# 737NG_CDU_MainPanel_v_01.net
KiCad netlist of a schematic drawn in EasyEDA
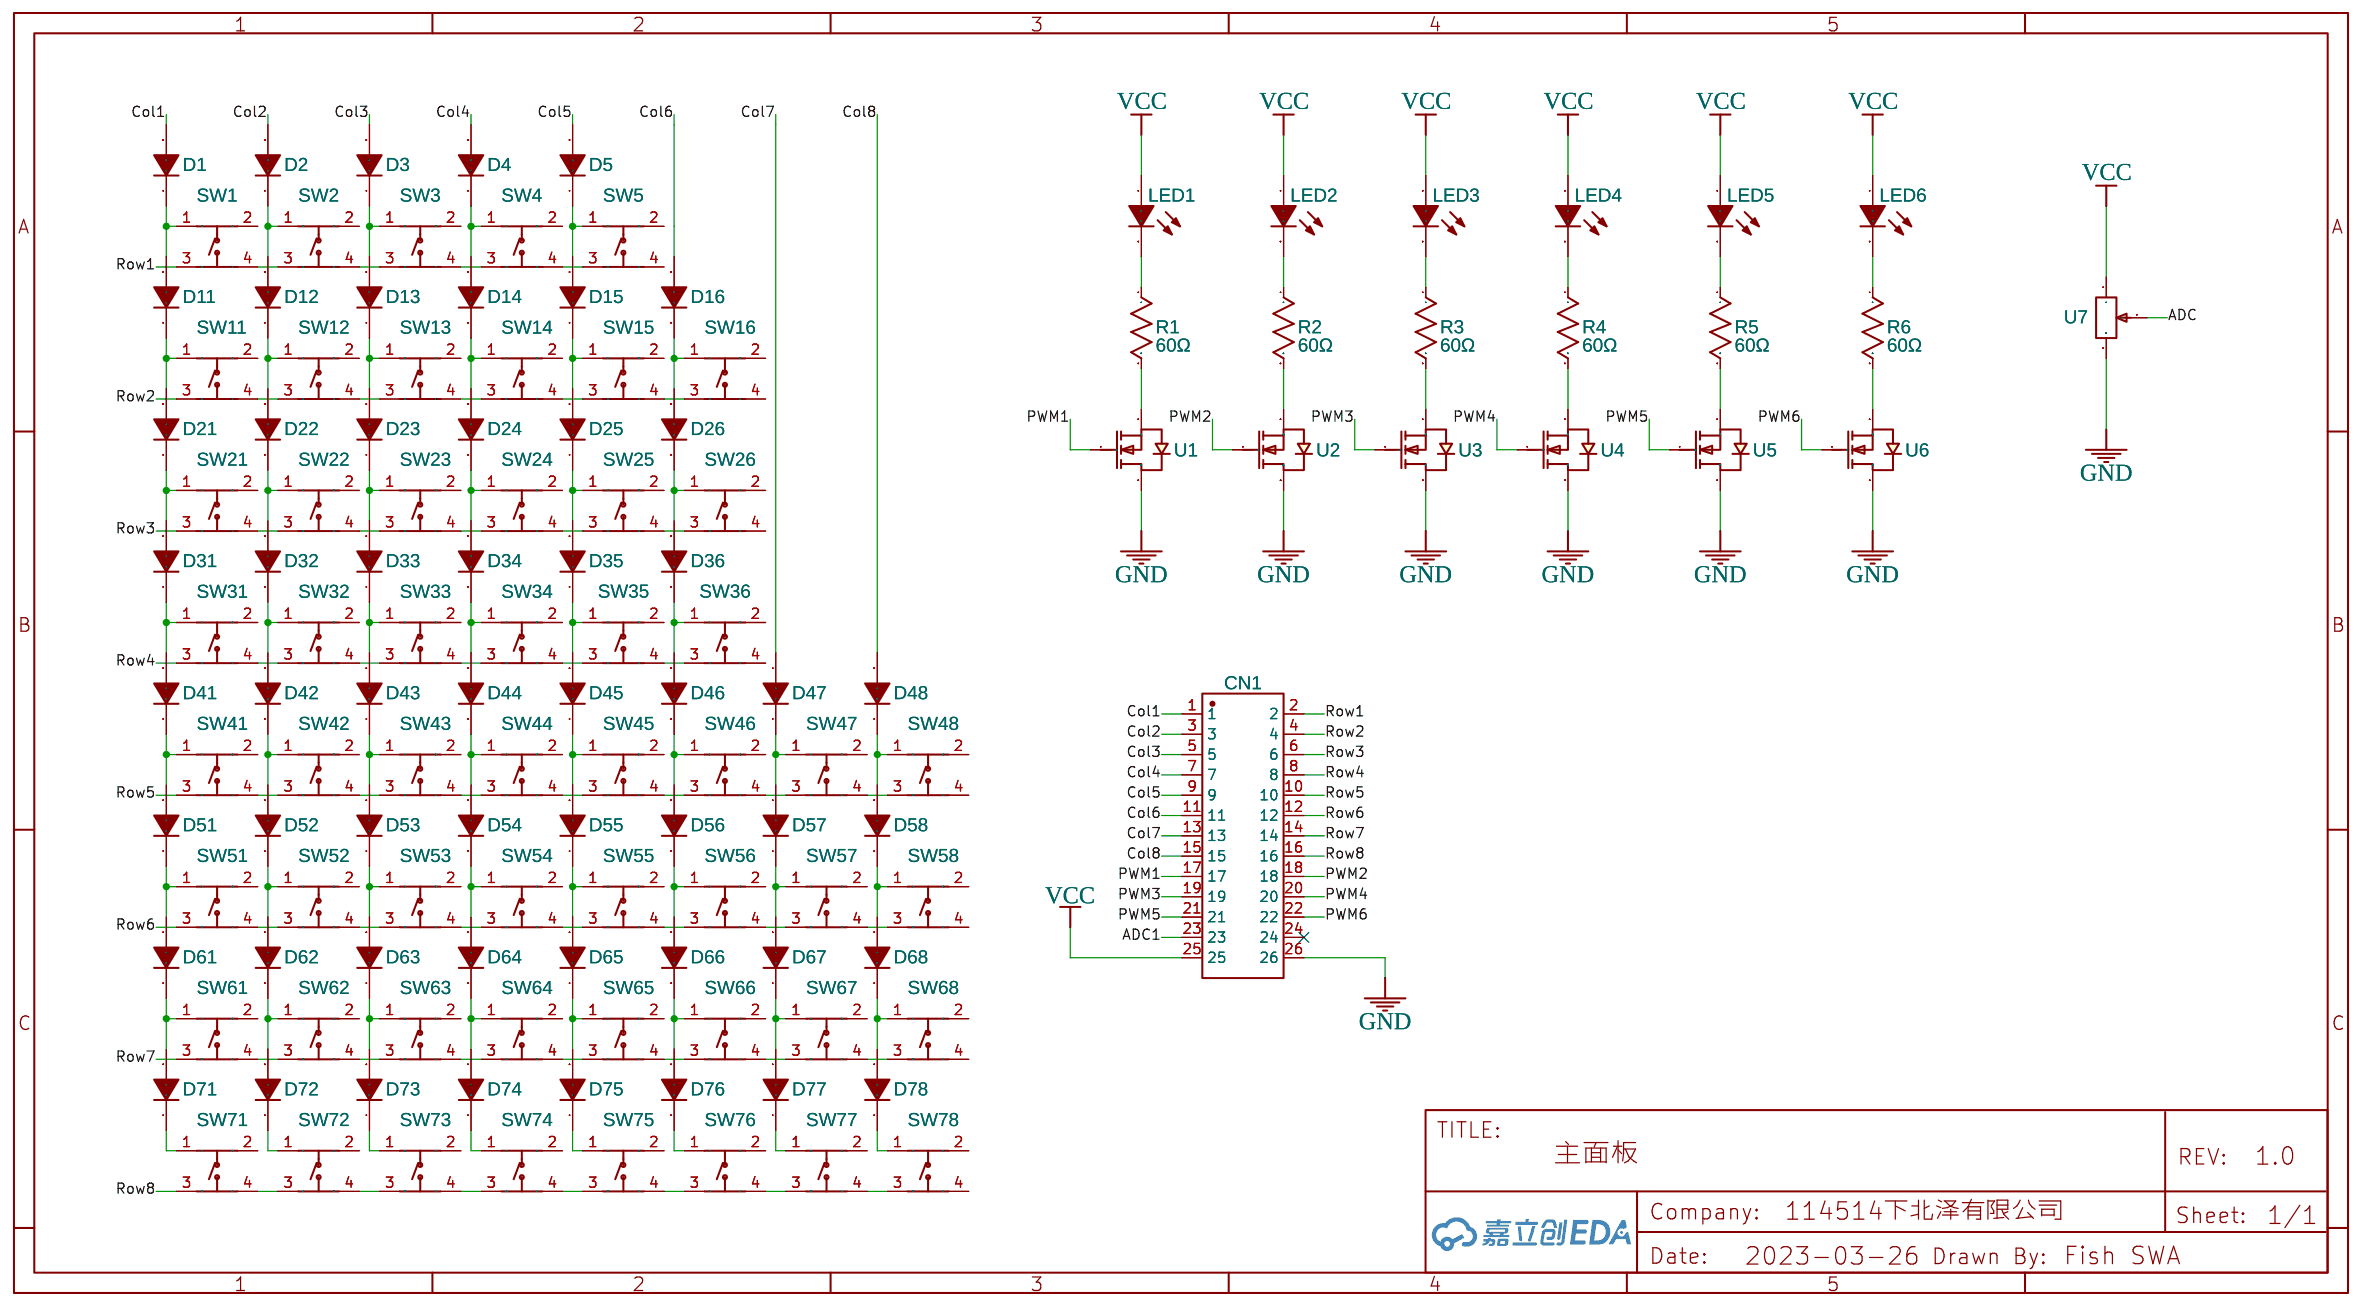
[diagram p0: schematic sheet]

(export (version "E")
  (design (tool "Eeschema 10.0.6"))
  (components
    (comp (ref "CN1")
      (value "A2004WV-2X13P")
      (fields (field (name "BOM_Supplier Part") "C465323"))
      (libsource (lib "") (part "A2004WV-2X13P"))
    )
    (comp (ref "D1")
      (value "1N4148WS T4")
      (fields (field (name "BOM_Manufacturer Part") "1N4148WS") (field (name "BOM_Supplier Part") "C2128"))
      (libsource (lib "") (part "1N4148WS T4"))
    )
    (comp (ref "D2")
      (value "1N4148WS T4")
      (fields (field (name "BOM_Manufacturer Part") "1N4148WS") (field (name "BOM_Supplier Part") "C2128"))
      (libsource (lib "") (part "1N4148WS T4"))
    )
    (comp (ref "D3")
      (value "1N4148WS T4")
      (fields (field (name "BOM_Manufacturer Part") "1N4148WS") (field (name "BOM_Supplier Part") "C2128"))
      (libsource (lib "") (part "1N4148WS T4"))
    )
    (comp (ref "D4")
      (value "1N4148WS T4")
      (fields (field (name "BOM_Manufacturer Part") "1N4148WS") (field (name "BOM_Supplier Part") "C2128"))
      (libsource (lib "") (part "1N4148WS T4"))
    )
    (comp (ref "D5")
      (value "1N4148WS T4")
      (fields (field (name "BOM_Manufacturer Part") "1N4148WS") (field (name "BOM_Supplier Part") "C2128"))
      (libsource (lib "") (part "1N4148WS T4"))
    )
    (comp (ref "D11")
      (value "1N4148WS T4")
      (fields (field (name "BOM_Manufacturer Part") "1N4148WS") (field (name "BOM_Supplier Part") "C2128"))
      (libsource (lib "") (part "1N4148WS T4"))
    )
    (comp (ref "D12")
      (value "1N4148WS T4")
      (fields (field (name "BOM_Manufacturer Part") "1N4148WS") (field (name "BOM_Supplier Part") "C2128"))
      (libsource (lib "") (part "1N4148WS T4"))
    )
    (comp (ref "D13")
      (value "1N4148WS T4")
      (fields (field (name "BOM_Manufacturer Part") "1N4148WS") (field (name "BOM_Supplier Part") "C2128"))
      (libsource (lib "") (part "1N4148WS T4"))
    )
    (comp (ref "D14")
      (value "1N4148WS T4")
      (fields (field (name "BOM_Manufacturer Part") "1N4148WS") (field (name "BOM_Supplier Part") "C2128"))
      (libsource (lib "") (part "1N4148WS T4"))
    )
    (comp (ref "D15")
      (value "1N4148WS T4")
      (fields (field (name "BOM_Manufacturer Part") "1N4148WS") (field (name "BOM_Supplier Part") "C2128"))
      (libsource (lib "") (part "1N4148WS T4"))
    )
    (comp (ref "D16")
      (value "1N4148WS T4")
      (fields (field (name "BOM_Manufacturer Part") "1N4148WS") (field (name "BOM_Supplier Part") "C2128"))
      (libsource (lib "") (part "1N4148WS T4"))
    )
    (comp (ref "D21")
      (value "1N4148WS T4")
      (fields (field (name "BOM_Manufacturer Part") "1N4148WS") (field (name "BOM_Supplier Part") "C2128"))
      (libsource (lib "") (part "1N4148WS T4"))
    )
    (comp (ref "D22")
      (value "1N4148WS T4")
      (fields (field (name "BOM_Manufacturer Part") "1N4148WS") (field (name "BOM_Supplier Part") "C2128"))
      (libsource (lib "") (part "1N4148WS T4"))
    )
    (comp (ref "D23")
      (value "1N4148WS T4")
      (fields (field (name "BOM_Manufacturer Part") "1N4148WS") (field (name "BOM_Supplier Part") "C2128"))
      (libsource (lib "") (part "1N4148WS T4"))
    )
    (comp (ref "D24")
      (value "1N4148WS T4")
      (fields (field (name "BOM_Manufacturer Part") "1N4148WS") (field (name "BOM_Supplier Part") "C2128"))
      (libsource (lib "") (part "1N4148WS T4"))
    )
    (comp (ref "D25")
      (value "1N4148WS T4")
      (fields (field (name "BOM_Manufacturer Part") "1N4148WS") (field (name "BOM_Supplier Part") "C2128"))
      (libsource (lib "") (part "1N4148WS T4"))
    )
    (comp (ref "D26")
      (value "1N4148WS T4")
      (fields (field (name "BOM_Manufacturer Part") "1N4148WS") (field (name "BOM_Supplier Part") "C2128"))
      (libsource (lib "") (part "1N4148WS T4"))
    )
    (comp (ref "D31")
      (value "1N4148WS T4")
      (fields (field (name "BOM_Manufacturer Part") "1N4148WS") (field (name "BOM_Supplier Part") "C2128"))
      (libsource (lib "") (part "1N4148WS T4"))
    )
    (comp (ref "D32")
      (value "1N4148WS T4")
      (fields (field (name "BOM_Manufacturer Part") "1N4148WS") (field (name "BOM_Supplier Part") "C2128"))
      (libsource (lib "") (part "1N4148WS T4"))
    )
    (comp (ref "D33")
      (value "1N4148WS T4")
      (fields (field (name "BOM_Manufacturer Part") "1N4148WS") (field (name "BOM_Supplier Part") "C2128"))
      (libsource (lib "") (part "1N4148WS T4"))
    )
    (comp (ref "D34")
      (value "1N4148WS T4")
      (fields (field (name "BOM_Manufacturer Part") "1N4148WS") (field (name "BOM_Supplier Part") "C2128"))
      (libsource (lib "") (part "1N4148WS T4"))
    )
    (comp (ref "D35")
      (value "1N4148WS T4")
      (fields (field (name "BOM_Manufacturer Part") "1N4148WS") (field (name "BOM_Supplier Part") "C2128"))
      (libsource (lib "") (part "1N4148WS T4"))
    )
    (comp (ref "D36")
      (value "1N4148WS T4")
      (fields (field (name "BOM_Manufacturer Part") "1N4148WS") (field (name "BOM_Supplier Part") "C2128"))
      (libsource (lib "") (part "1N4148WS T4"))
    )
    (comp (ref "D41")
      (value "1N4148WS T4")
      (fields (field (name "BOM_Manufacturer Part") "1N4148WS") (field (name "BOM_Supplier Part") "C2128"))
      (libsource (lib "") (part "1N4148WS T4"))
    )
    (comp (ref "D42")
      (value "1N4148WS T4")
      (fields (field (name "BOM_Manufacturer Part") "1N4148WS") (field (name "BOM_Supplier Part") "C2128"))
      (libsource (lib "") (part "1N4148WS T4"))
    )
    (comp (ref "D43")
      (value "1N4148WS T4")
      (fields (field (name "BOM_Manufacturer Part") "1N4148WS") (field (name "BOM_Supplier Part") "C2128"))
      (libsource (lib "") (part "1N4148WS T4"))
    )
    (comp (ref "D44")
      (value "1N4148WS T4")
      (fields (field (name "BOM_Manufacturer Part") "1N4148WS") (field (name "BOM_Supplier Part") "C2128"))
      (libsource (lib "") (part "1N4148WS T4"))
    )
    (comp (ref "D45")
      (value "1N4148WS T4")
      (fields (field (name "BOM_Manufacturer Part") "1N4148WS") (field (name "BOM_Supplier Part") "C2128"))
      (libsource (lib "") (part "1N4148WS T4"))
    )
    (comp (ref "D46")
      (value "1N4148WS T4")
      (fields (field (name "BOM_Manufacturer Part") "1N4148WS") (field (name "BOM_Supplier Part") "C2128"))
      (libsource (lib "") (part "1N4148WS T4"))
    )
    (comp (ref "D47")
      (value "1N4148WS T4")
      (fields (field (name "BOM_Manufacturer Part") "1N4148WS") (field (name "BOM_Supplier Part") "C2128"))
      (libsource (lib "") (part "1N4148WS T4"))
    )
    (comp (ref "D48")
      (value "1N4148WS T4")
      (fields (field (name "BOM_Manufacturer Part") "1N4148WS") (field (name "BOM_Supplier Part") "C2128"))
      (libsource (lib "") (part "1N4148WS T4"))
    )
    (comp (ref "D51")
      (value "1N4148WS T4")
      (fields (field (name "BOM_Manufacturer Part") "1N4148WS") (field (name "BOM_Supplier Part") "C2128"))
      (libsource (lib "") (part "1N4148WS T4"))
    )
    (comp (ref "D52")
      (value "1N4148WS T4")
      (fields (field (name "BOM_Manufacturer Part") "1N4148WS") (field (name "BOM_Supplier Part") "C2128"))
      (libsource (lib "") (part "1N4148WS T4"))
    )
    (comp (ref "D53")
      (value "1N4148WS T4")
      (fields (field (name "BOM_Manufacturer Part") "1N4148WS") (field (name "BOM_Supplier Part") "C2128"))
      (libsource (lib "") (part "1N4148WS T4"))
    )
    (comp (ref "D54")
      (value "1N4148WS T4")
      (fields (field (name "BOM_Manufacturer Part") "1N4148WS") (field (name "BOM_Supplier Part") "C2128"))
      (libsource (lib "") (part "1N4148WS T4"))
    )
    (comp (ref "D55")
      (value "1N4148WS T4")
      (fields (field (name "BOM_Manufacturer Part") "1N4148WS") (field (name "BOM_Supplier Part") "C2128"))
      (libsource (lib "") (part "1N4148WS T4"))
    )
    (comp (ref "D56")
      (value "1N4148WS T4")
      (fields (field (name "BOM_Manufacturer Part") "1N4148WS") (field (name "BOM_Supplier Part") "C2128"))
      (libsource (lib "") (part "1N4148WS T4"))
    )
    (comp (ref "D57")
      (value "1N4148WS T4")
      (fields (field (name "BOM_Manufacturer Part") "1N4148WS") (field (name "BOM_Supplier Part") "C2128"))
      (libsource (lib "") (part "1N4148WS T4"))
    )
    (comp (ref "D58")
      (value "1N4148WS T4")
      (fields (field (name "BOM_Manufacturer Part") "1N4148WS") (field (name "BOM_Supplier Part") "C2128"))
      (libsource (lib "") (part "1N4148WS T4"))
    )
    (comp (ref "D61")
      (value "1N4148WS T4")
      (fields (field (name "BOM_Manufacturer Part") "1N4148WS") (field (name "BOM_Supplier Part") "C2128"))
      (libsource (lib "") (part "1N4148WS T4"))
    )
    (comp (ref "D62")
      (value "1N4148WS T4")
      (fields (field (name "BOM_Manufacturer Part") "1N4148WS") (field (name "BOM_Supplier Part") "C2128"))
      (libsource (lib "") (part "1N4148WS T4"))
    )
    (comp (ref "D63")
      (value "1N4148WS T4")
      (fields (field (name "BOM_Manufacturer Part") "1N4148WS") (field (name "BOM_Supplier Part") "C2128"))
      (libsource (lib "") (part "1N4148WS T4"))
    )
    (comp (ref "D64")
      (value "1N4148WS T4")
      (fields (field (name "BOM_Manufacturer Part") "1N4148WS") (field (name "BOM_Supplier Part") "C2128"))
      (libsource (lib "") (part "1N4148WS T4"))
    )
    (comp (ref "D65")
      (value "1N4148WS T4")
      (fields (field (name "BOM_Manufacturer Part") "1N4148WS") (field (name "BOM_Supplier Part") "C2128"))
      (libsource (lib "") (part "1N4148WS T4"))
    )
    (comp (ref "D66")
      (value "1N4148WS T4")
      (fields (field (name "BOM_Manufacturer Part") "1N4148WS") (field (name "BOM_Supplier Part") "C2128"))
      (libsource (lib "") (part "1N4148WS T4"))
    )
    (comp (ref "D67")
      (value "1N4148WS T4")
      (fields (field (name "BOM_Manufacturer Part") "1N4148WS") (field (name "BOM_Supplier Part") "C2128"))
      (libsource (lib "") (part "1N4148WS T4"))
    )
    (comp (ref "D68")
      (value "1N4148WS T4")
      (fields (field (name "BOM_Manufacturer Part") "1N4148WS") (field (name "BOM_Supplier Part") "C2128"))
      (libsource (lib "") (part "1N4148WS T4"))
    )
    (comp (ref "D71")
      (value "1N4148WS T4")
      (fields (field (name "BOM_Manufacturer Part") "1N4148WS") (field (name "BOM_Supplier Part") "C2128"))
      (libsource (lib "") (part "1N4148WS T4"))
    )
    (comp (ref "D72")
      (value "1N4148WS T4")
      (fields (field (name "BOM_Manufacturer Part") "1N4148WS") (field (name "BOM_Supplier Part") "C2128"))
      (libsource (lib "") (part "1N4148WS T4"))
    )
    (comp (ref "D73")
      (value "1N4148WS T4")
      (fields (field (name "BOM_Manufacturer Part") "1N4148WS") (field (name "BOM_Supplier Part") "C2128"))
      (libsource (lib "") (part "1N4148WS T4"))
    )
    (comp (ref "D74")
      (value "1N4148WS T4")
      (fields (field (name "BOM_Manufacturer Part") "1N4148WS") (field (name "BOM_Supplier Part") "C2128"))
      (libsource (lib "") (part "1N4148WS T4"))
    )
    (comp (ref "D75")
      (value "1N4148WS T4")
      (fields (field (name "BOM_Manufacturer Part") "1N4148WS") (field (name "BOM_Supplier Part") "C2128"))
      (libsource (lib "") (part "1N4148WS T4"))
    )
    (comp (ref "D76")
      (value "1N4148WS T4")
      (fields (field (name "BOM_Manufacturer Part") "1N4148WS") (field (name "BOM_Supplier Part") "C2128"))
      (libsource (lib "") (part "1N4148WS T4"))
    )
    (comp (ref "D77")
      (value "1N4148WS T4")
      (fields (field (name "BOM_Manufacturer Part") "1N4148WS") (field (name "BOM_Supplier Part") "C2128"))
      (libsource (lib "") (part "1N4148WS T4"))
    )
    (comp (ref "D78")
      (value "1N4148WS T4")
      (fields (field (name "BOM_Manufacturer Part") "1N4148WS") (field (name "BOM_Supplier Part") "C2128"))
      (libsource (lib "") (part "1N4148WS T4"))
    )
    (comp (ref "LED1")
      (value "SML-H12P8TT86")
      (fields (field (name "BOM_Supplier Part") "C510035"))
      (libsource (lib "") (part "SML-H12P8TT86"))
    )
    (comp (ref "LED2")
      (value "SML-H12P8TT86")
      (fields (field (name "BOM_Supplier Part") "C510035"))
      (libsource (lib "") (part "SML-H12P8TT86"))
    )
    (comp (ref "LED3")
      (value "SML-H12P8TT86")
      (fields (field (name "BOM_Supplier Part") "C510035"))
      (libsource (lib "") (part "SML-H12P8TT86"))
    )
    (comp (ref "LED4")
      (value "SML-H12P8TT86")
      (fields (field (name "BOM_Supplier Part") "C510035"))
      (libsource (lib "") (part "SML-H12P8TT86"))
    )
    (comp (ref "LED5")
      (value "SML-H12P8TT86")
      (fields (field (name "BOM_Supplier Part") "C510035"))
      (libsource (lib "") (part "SML-H12P8TT86"))
    )
    (comp (ref "LED6")
      (value "SML-H12P8TT86")
      (fields (field (name "BOM_Supplier Part") "C510035"))
      (libsource (lib "") (part "SML-H12P8TT86"))
    )
    (comp (ref "R1") (value "60Ω") (libsource (lib "") (part "R_0805_US")))
    (comp (ref "R2") (value "60Ω") (libsource (lib "") (part "R_0805_US")))
    (comp (ref "R3") (value "60Ω") (libsource (lib "") (part "R_0805_US")))
    (comp (ref "R4") (value "60Ω") (libsource (lib "") (part "R_0805_US")))
    (comp (ref "R5") (value "60Ω") (libsource (lib "") (part "R_0805_US")))
    (comp (ref "R6") (value "60Ω") (libsource (lib "") (part "R_0805_US")))
    (comp (ref "SW1")
      (value "PTS525SM15SMTR2LFS")
      (fields (field (name "BOM_Supplier Part") "C221856"))
      (libsource (lib "") (part "PTS525SM15SMTR2LFS"))
    )
    (comp (ref "SW2")
      (value "PTS525SM15SMTR2LFS")
      (fields (field (name "BOM_Supplier Part") "C221856"))
      (libsource (lib "") (part "PTS525SM15SMTR2LFS"))
    )
    (comp (ref "SW3")
      (value "PTS525SM15SMTR2LFS")
      (fields (field (name "BOM_Supplier Part") "C221856"))
      (libsource (lib "") (part "PTS525SM15SMTR2LFS"))
    )
    (comp (ref "SW4")
      (value "PTS525SM15SMTR2LFS")
      (fields (field (name "BOM_Supplier Part") "C221856"))
      (libsource (lib "") (part "PTS525SM15SMTR2LFS"))
    )
    (comp (ref "SW5")
      (value "PTS525SM15SMTR2LFS")
      (fields (field (name "BOM_Supplier Part") "C221856"))
      (libsource (lib "") (part "PTS525SM15SMTR2LFS"))
    )
    (comp (ref "SW11")
      (value "PTS525SM15SMTR2LFS")
      (fields (field (name "BOM_Supplier Part") "C221856"))
      (libsource (lib "") (part "PTS525SM15SMTR2LFS"))
    )
    (comp (ref "SW12")
      (value "PTS525SM15SMTR2LFS")
      (fields (field (name "BOM_Supplier Part") "C221856"))
      (libsource (lib "") (part "PTS525SM15SMTR2LFS"))
    )
    (comp (ref "SW13")
      (value "PTS525SM15SMTR2LFS")
      (fields (field (name "BOM_Supplier Part") "C221856"))
      (libsource (lib "") (part "PTS525SM15SMTR2LFS"))
    )
    (comp (ref "SW14")
      (value "PTS525SM15SMTR2LFS")
      (fields (field (name "BOM_Supplier Part") "C221856"))
      (libsource (lib "") (part "PTS525SM15SMTR2LFS"))
    )
    (comp (ref "SW15")
      (value "PTS525SM15SMTR2LFS")
      (fields (field (name "BOM_Supplier Part") "C221856"))
      (libsource (lib "") (part "PTS525SM15SMTR2LFS"))
    )
    (comp (ref "SW16")
      (value "PTS525SM15SMTR2LFS")
      (fields (field (name "BOM_Supplier Part") "C221856"))
      (libsource (lib "") (part "PTS525SM15SMTR2LFS"))
    )
    (comp (ref "SW21")
      (value "PTS525SM15SMTR2LFS")
      (fields (field (name "BOM_Supplier Part") "C221856"))
      (libsource (lib "") (part "PTS525SM15SMTR2LFS"))
    )
    (comp (ref "SW22")
      (value "PTS525SM15SMTR2LFS")
      (fields (field (name "BOM_Supplier Part") "C221856"))
      (libsource (lib "") (part "PTS525SM15SMTR2LFS"))
    )
    (comp (ref "SW23")
      (value "PTS525SM15SMTR2LFS")
      (fields (field (name "BOM_Supplier Part") "C221856"))
      (libsource (lib "") (part "PTS525SM15SMTR2LFS"))
    )
    (comp (ref "SW24")
      (value "PTS525SM15SMTR2LFS")
      (fields (field (name "BOM_Supplier Part") "C221856"))
      (libsource (lib "") (part "PTS525SM15SMTR2LFS"))
    )
    (comp (ref "SW25")
      (value "PTS525SM15SMTR2LFS")
      (fields (field (name "BOM_Supplier Part") "C221856"))
      (libsource (lib "") (part "PTS525SM15SMTR2LFS"))
    )
    (comp (ref "SW26")
      (value "PTS525SM15SMTR2LFS")
      (fields (field (name "BOM_Supplier Part") "C221856"))
      (libsource (lib "") (part "PTS525SM15SMTR2LFS"))
    )
    (comp (ref "SW31")
      (value "PTS525SM15SMTR2LFS")
      (fields (field (name "BOM_Supplier Part") "C221856"))
      (libsource (lib "") (part "PTS525SM15SMTR2LFS"))
    )
    (comp (ref "SW32")
      (value "PTS525SM15SMTR2LFS")
      (fields (field (name "BOM_Supplier Part") "C221856"))
      (libsource (lib "") (part "PTS525SM15SMTR2LFS"))
    )
    (comp (ref "SW33")
      (value "PTS525SM15SMTR2LFS")
      (fields (field (name "BOM_Supplier Part") "C221856"))
      (libsource (lib "") (part "PTS525SM15SMTR2LFS"))
    )
    (comp (ref "SW34")
      (value "PTS525SM15SMTR2LFS")
      (fields (field (name "BOM_Supplier Part") "C221856"))
      (libsource (lib "") (part "PTS525SM15SMTR2LFS"))
    )
    (comp (ref "SW35")
      (value "PTS525SM15SMTR2LFS")
      (fields (field (name "BOM_Supplier Part") "C221856"))
      (libsource (lib "") (part "PTS525SM15SMTR2LFS"))
    )
    (comp (ref "SW36")
      (value "PTS525SM15SMTR2LFS")
      (fields (field (name "BOM_Supplier Part") "C221856"))
      (libsource (lib "") (part "PTS525SM15SMTR2LFS"))
    )
    (comp (ref "SW41")
      (value "PTS525SM15SMTR2LFS")
      (fields (field (name "BOM_Supplier Part") "C221856"))
      (libsource (lib "") (part "PTS525SM15SMTR2LFS"))
    )
    (comp (ref "SW42")
      (value "PTS525SM15SMTR2LFS")
      (fields (field (name "BOM_Supplier Part") "C221856"))
      (libsource (lib "") (part "PTS525SM15SMTR2LFS"))
    )
    (comp (ref "SW43")
      (value "PTS525SM15SMTR2LFS")
      (fields (field (name "BOM_Supplier Part") "C221856"))
      (libsource (lib "") (part "PTS525SM15SMTR2LFS"))
    )
    (comp (ref "SW44")
      (value "PTS525SM15SMTR2LFS")
      (fields (field (name "BOM_Supplier Part") "C221856"))
      (libsource (lib "") (part "PTS525SM15SMTR2LFS"))
    )
    (comp (ref "SW45")
      (value "PTS525SM15SMTR2LFS")
      (fields (field (name "BOM_Supplier Part") "C221856"))
      (libsource (lib "") (part "PTS525SM15SMTR2LFS"))
    )
    (comp (ref "SW46")
      (value "PTS525SM15SMTR2LFS")
      (fields (field (name "BOM_Supplier Part") "C221856"))
      (libsource (lib "") (part "PTS525SM15SMTR2LFS"))
    )
    (comp (ref "SW47")
      (value "PTS525SM15SMTR2LFS")
      (fields (field (name "BOM_Supplier Part") "C221856"))
      (libsource (lib "") (part "PTS525SM15SMTR2LFS"))
    )
    (comp (ref "SW48")
      (value "PTS525SM15SMTR2LFS")
      (fields (field (name "BOM_Supplier Part") "C221856"))
      (libsource (lib "") (part "PTS525SM15SMTR2LFS"))
    )
    (comp (ref "SW51")
      (value "PTS525SM15SMTR2LFS")
      (fields (field (name "BOM_Supplier Part") "C221856"))
      (libsource (lib "") (part "PTS525SM15SMTR2LFS"))
    )
    (comp (ref "SW52")
      (value "PTS525SM15SMTR2LFS")
      (fields (field (name "BOM_Supplier Part") "C221856"))
      (libsource (lib "") (part "PTS525SM15SMTR2LFS"))
    )
    (comp (ref "SW53")
      (value "PTS525SM15SMTR2LFS")
      (fields (field (name "BOM_Supplier Part") "C221856"))
      (libsource (lib "") (part "PTS525SM15SMTR2LFS"))
    )
    (comp (ref "SW54")
      (value "PTS525SM15SMTR2LFS")
      (fields (field (name "BOM_Supplier Part") "C221856"))
      (libsource (lib "") (part "PTS525SM15SMTR2LFS"))
    )
    (comp (ref "SW55")
      (value "PTS525SM15SMTR2LFS")
      (fields (field (name "BOM_Supplier Part") "C221856"))
      (libsource (lib "") (part "PTS525SM15SMTR2LFS"))
    )
    (comp (ref "SW56")
      (value "PTS525SM15SMTR2LFS")
      (fields (field (name "BOM_Supplier Part") "C221856"))
      (libsource (lib "") (part "PTS525SM15SMTR2LFS"))
    )
    (comp (ref "SW57")
      (value "PTS525SM15SMTR2LFS")
      (fields (field (name "BOM_Supplier Part") "C221856"))
      (libsource (lib "") (part "PTS525SM15SMTR2LFS"))
    )
    (comp (ref "SW58")
      (value "PTS525SM15SMTR2LFS")
      (fields (field (name "BOM_Supplier Part") "C221856"))
      (libsource (lib "") (part "PTS525SM15SMTR2LFS"))
    )
    (comp (ref "SW61")
      (value "PTS525SM15SMTR2LFS")
      (fields (field (name "BOM_Supplier Part") "C221856"))
      (libsource (lib "") (part "PTS525SM15SMTR2LFS"))
    )
    (comp (ref "SW62")
      (value "PTS525SM15SMTR2LFS")
      (fields (field (name "BOM_Supplier Part") "C221856"))
      (libsource (lib "") (part "PTS525SM15SMTR2LFS"))
    )
    (comp (ref "SW63")
      (value "PTS525SM15SMTR2LFS")
      (fields (field (name "BOM_Supplier Part") "C221856"))
      (libsource (lib "") (part "PTS525SM15SMTR2LFS"))
    )
    (comp (ref "SW64")
      (value "PTS525SM15SMTR2LFS")
      (fields (field (name "BOM_Supplier Part") "C221856"))
      (libsource (lib "") (part "PTS525SM15SMTR2LFS"))
    )
    (comp (ref "SW65")
      (value "PTS525SM15SMTR2LFS")
      (fields (field (name "BOM_Supplier Part") "C221856"))
      (libsource (lib "") (part "PTS525SM15SMTR2LFS"))
    )
    (comp (ref "SW66")
      (value "PTS525SM15SMTR2LFS")
      (fields (field (name "BOM_Supplier Part") "C221856"))
      (libsource (lib "") (part "PTS525SM15SMTR2LFS"))
    )
    (comp (ref "SW67")
      (value "PTS525SM15SMTR2LFS")
      (fields (field (name "BOM_Supplier Part") "C221856"))
      (libsource (lib "") (part "PTS525SM15SMTR2LFS"))
    )
    (comp (ref "SW68")
      (value "PTS525SM15SMTR2LFS")
      (fields (field (name "BOM_Supplier Part") "C221856"))
      (libsource (lib "") (part "PTS525SM15SMTR2LFS"))
    )
    (comp (ref "SW71")
      (value "PTS525SM15SMTR2LFS")
      (fields (field (name "BOM_Supplier Part") "C221856"))
      (libsource (lib "") (part "PTS525SM15SMTR2LFS"))
    )
    (comp (ref "SW72")
      (value "PTS525SM15SMTR2LFS")
      (fields (field (name "BOM_Supplier Part") "C221856"))
      (libsource (lib "") (part "PTS525SM15SMTR2LFS"))
    )
    (comp (ref "SW73")
      (value "PTS525SM15SMTR2LFS")
      (fields (field (name "BOM_Supplier Part") "C221856"))
      (libsource (lib "") (part "PTS525SM15SMTR2LFS"))
    )
    (comp (ref "SW74")
      (value "PTS525SM15SMTR2LFS")
      (fields (field (name "BOM_Supplier Part") "C221856"))
      (libsource (lib "") (part "PTS525SM15SMTR2LFS"))
    )
    (comp (ref "SW75")
      (value "PTS525SM15SMTR2LFS")
      (fields (field (name "BOM_Supplier Part") "C221856"))
      (libsource (lib "") (part "PTS525SM15SMTR2LFS"))
    )
    (comp (ref "SW76")
      (value "PTS525SM15SMTR2LFS")
      (fields (field (name "BOM_Supplier Part") "C221856"))
      (libsource (lib "") (part "PTS525SM15SMTR2LFS"))
    )
    (comp (ref "SW77")
      (value "PTS525SM15SMTR2LFS")
      (fields (field (name "BOM_Supplier Part") "C221856"))
      (libsource (lib "") (part "PTS525SM15SMTR2LFS"))
    )
    (comp (ref "SW78")
      (value "PTS525SM15SMTR2LFS")
      (fields (field (name "BOM_Supplier Part") "C221856"))
      (libsource (lib "") (part "PTS525SM15SMTR2LFS"))
    )
    (comp (ref "U1")
      (value "5N10_C5140036")
      (fields (field (name "BOM_Manufacturer Part") "5N10-MS") (field (name "BOM_Supplier Part") "C5140036"))
      (libsource (lib "") (part "5N10_C5140036"))
    )
    (comp (ref "U2")
      (value "5N10_C5140036")
      (fields (field (name "BOM_Manufacturer Part") "5N10-MS") (field (name "BOM_Supplier Part") "C5140036"))
      (libsource (lib "") (part "5N10_C5140036"))
    )
    (comp (ref "U3")
      (value "5N10_C5140036")
      (fields (field (name "BOM_Manufacturer Part") "5N10-MS") (field (name "BOM_Supplier Part") "C5140036"))
      (libsource (lib "") (part "5N10_C5140036"))
    )
    (comp (ref "U4")
      (value "5N10_C5140036")
      (fields (field (name "BOM_Manufacturer Part") "5N10-MS") (field (name "BOM_Supplier Part") "C5140036"))
      (libsource (lib "") (part "5N10_C5140036"))
    )
    (comp (ref "U5")
      (value "5N10_C5140036")
      (fields (field (name "BOM_Manufacturer Part") "5N10-MS") (field (name "BOM_Supplier Part") "C5140036"))
      (libsource (lib "") (part "5N10_C5140036"))
    )
    (comp (ref "U6")
      (value "5N10_C5140036")
      (fields (field (name "BOM_Manufacturer Part") "5N10-MS") (field (name "BOM_Supplier Part") "C5140036"))
      (libsource (lib "") (part "5N10_C5140036"))
    )
    (comp (ref "U7")
      (value "WH06-2C-203(20K)")
      (fields (field (name "BOM_Supplier Part") "C5205044"))
      (libsource (lib "") (part "WH06-2C-203(20K)"))
    )
  )
  (nets
    (net (code "1") (name "/ADC") (class "Default")
      (node (ref "U7") (pin "2") (pinfunction "2_2") (pintype "input"))
    )
    (net (code "2") (name "/ADC1") (class "Default")
      (node (ref "CN1") (pin "23") (pinfunction "23_23") (pintype "unspecified"))
    )
    (net (code "3") (name "/Col1") (class "Default")
      (node (ref "CN1") (pin "1") (pinfunction "1_1") (pintype "unspecified"))
      (node (ref "D1") (pin "2") (pinfunction "A_2") (pintype "unspecified"))
    )
    (net (code "4") (name "/Col2") (class "Default")
      (node (ref "CN1") (pin "3") (pinfunction "3_3") (pintype "unspecified"))
      (node (ref "D2") (pin "2") (pinfunction "A_2") (pintype "unspecified"))
    )
    (net (code "5") (name "/Col3") (class "Default")
      (node (ref "CN1") (pin "5") (pinfunction "5_5") (pintype "unspecified"))
      (node (ref "D3") (pin "2") (pinfunction "A_2") (pintype "unspecified"))
    )
    (net (code "6") (name "/Col4") (class "Default")
      (node (ref "CN1") (pin "7") (pinfunction "7_7") (pintype "unspecified"))
      (node (ref "D4") (pin "2") (pinfunction "A_2") (pintype "unspecified"))
    )
    (net (code "7") (name "/Col5") (class "Default")
      (node (ref "CN1") (pin "9") (pinfunction "9_9") (pintype "unspecified"))
      (node (ref "D5") (pin "2") (pinfunction "A_2") (pintype "unspecified"))
    )
    (net (code "8") (name "/Col6") (class "Default")
      (node (ref "CN1") (pin "11") (pinfunction "11_11") (pintype "unspecified"))
      (node (ref "D16") (pin "2") (pinfunction "A_2") (pintype "unspecified"))
    )
    (net (code "9") (name "/Col7") (class "Default")
      (node (ref "CN1") (pin "13") (pinfunction "13_13") (pintype "unspecified"))
      (node (ref "D47") (pin "2") (pinfunction "A_2") (pintype "unspecified"))
    )
    (net (code "10") (name "/Col8") (class "Default")
      (node (ref "CN1") (pin "15") (pinfunction "15_15") (pintype "unspecified"))
      (node (ref "D48") (pin "2") (pinfunction "A_2") (pintype "unspecified"))
    )
    (net (code "11") (name "/PWM1") (class "Default")
      (node (ref "CN1") (pin "17") (pinfunction "17_17") (pintype "unspecified"))
      (node (ref "U1") (pin "1") (pinfunction "G_1") (pintype "unspecified"))
    )
    (net (code "12") (name "/PWM2") (class "Default")
      (node (ref "CN1") (pin "18") (pinfunction "18_18") (pintype "unspecified"))
      (node (ref "U2") (pin "1") (pinfunction "G_1") (pintype "unspecified"))
    )
    (net (code "13") (name "/PWM3") (class "Default")
      (node (ref "CN1") (pin "19") (pinfunction "19_19") (pintype "unspecified"))
      (node (ref "U3") (pin "1") (pinfunction "G_1") (pintype "unspecified"))
    )
    (net (code "14") (name "/PWM4") (class "Default")
      (node (ref "CN1") (pin "20") (pinfunction "20_20") (pintype "unspecified"))
      (node (ref "U4") (pin "1") (pinfunction "G_1") (pintype "unspecified"))
    )
    (net (code "15") (name "/PWM5") (class "Default")
      (node (ref "CN1") (pin "21") (pinfunction "21_21") (pintype "unspecified"))
      (node (ref "U5") (pin "1") (pinfunction "G_1") (pintype "unspecified"))
    )
    (net (code "16") (name "/PWM6") (class "Default")
      (node (ref "CN1") (pin "22") (pinfunction "22_22") (pintype "unspecified"))
      (node (ref "U6") (pin "1") (pinfunction "G_1") (pintype "unspecified"))
    )
    (net (code "17") (name "/Row1") (class "Default")
      (node (ref "CN1") (pin "2") (pinfunction "2_2") (pintype "unspecified"))
      (node (ref "SW1") (pin "3") (pinfunction "3_3") (pintype "unspecified"))
    )
    (net (code "18") (name "/Row2") (class "Default")
      (node (ref "CN1") (pin "4") (pinfunction "4_4") (pintype "unspecified"))
      (node (ref "SW11") (pin "3") (pinfunction "3_3") (pintype "unspecified"))
    )
    (net (code "19") (name "/Row3") (class "Default")
      (node (ref "CN1") (pin "6") (pinfunction "6_6") (pintype "unspecified"))
      (node (ref "SW21") (pin "3") (pinfunction "3_3") (pintype "unspecified"))
    )
    (net (code "20") (name "/Row4") (class "Default")
      (node (ref "CN1") (pin "8") (pinfunction "8_8") (pintype "unspecified"))
      (node (ref "SW31") (pin "3") (pinfunction "3_3") (pintype "unspecified"))
    )
    (net (code "21") (name "/Row5") (class "Default")
      (node (ref "CN1") (pin "10") (pinfunction "10_10") (pintype "unspecified"))
      (node (ref "SW41") (pin "3") (pinfunction "3_3") (pintype "unspecified"))
    )
    (net (code "22") (name "/Row6") (class "Default")
      (node (ref "CN1") (pin "12") (pinfunction "12_12") (pintype "unspecified"))
      (node (ref "SW51") (pin "3") (pinfunction "3_3") (pintype "unspecified"))
    )
    (net (code "23") (name "/Row7") (class "Default")
      (node (ref "CN1") (pin "14") (pinfunction "14_14") (pintype "unspecified"))
      (node (ref "SW61") (pin "3") (pinfunction "3_3") (pintype "unspecified"))
    )
    (net (code "24") (name "/Row8") (class "Default")
      (node (ref "CN1") (pin "16") (pinfunction "16_16") (pintype "unspecified"))
      (node (ref "SW71") (pin "3") (pinfunction "3_3") (pintype "unspecified"))
    )
    (net (code "25") (name "GND") (class "Default")
      (node (ref "CN1") (pin "26") (pinfunction "26_26") (pintype "unspecified"))
      (node (ref "U1") (pin "3") (pinfunction "D_3") (pintype "unspecified"))
      (node (ref "U2") (pin "3") (pinfunction "D_3") (pintype "unspecified"))
      (node (ref "U3") (pin "3") (pinfunction "D_3") (pintype "unspecified"))
      (node (ref "U4") (pin "3") (pinfunction "D_3") (pintype "unspecified"))
      (node (ref "U5") (pin "3") (pinfunction "D_3") (pintype "unspecified"))
      (node (ref "U6") (pin "3") (pinfunction "D_3") (pintype "unspecified"))
      (node (ref "U7") (pin "3") (pinfunction "3_3") (pintype "input"))
    )
    (net (code "26") (name "Net-(D1-K)") (class "Default")
      (node (ref "D1") (pin "1") (pinfunction "K_1") (pintype "unspecified"))
      (node (ref "D11") (pin "2") (pinfunction "A_2") (pintype "unspecified"))
      (node (ref "SW1") (pin "1") (pinfunction "1_1") (pintype "unspecified"))
    )
    (net (code "27") (name "Net-(D11-K)") (class "Default")
      (node (ref "D11") (pin "1") (pinfunction "K_1") (pintype "unspecified"))
      (node (ref "D21") (pin "2") (pinfunction "A_2") (pintype "unspecified"))
      (node (ref "SW11") (pin "1") (pinfunction "1_1") (pintype "unspecified"))
    )
    (net (code "28") (name "Net-(D12-A)") (class "Default")
      (node (ref "D12") (pin "2") (pinfunction "A_2") (pintype "unspecified"))
      (node (ref "D2") (pin "1") (pinfunction "K_1") (pintype "unspecified"))
      (node (ref "SW2") (pin "1") (pinfunction "1_1") (pintype "unspecified"))
    )
    (net (code "29") (name "Net-(D12-K)") (class "Default")
      (node (ref "D12") (pin "1") (pinfunction "K_1") (pintype "unspecified"))
      (node (ref "D22") (pin "2") (pinfunction "A_2") (pintype "unspecified"))
      (node (ref "SW12") (pin "1") (pinfunction "1_1") (pintype "unspecified"))
    )
    (net (code "30") (name "Net-(D13-A)") (class "Default")
      (node (ref "D13") (pin "2") (pinfunction "A_2") (pintype "unspecified"))
      (node (ref "D3") (pin "1") (pinfunction "K_1") (pintype "unspecified"))
      (node (ref "SW3") (pin "1") (pinfunction "1_1") (pintype "unspecified"))
    )
    (net (code "31") (name "Net-(D13-K)") (class "Default")
      (node (ref "D13") (pin "1") (pinfunction "K_1") (pintype "unspecified"))
      (node (ref "D23") (pin "2") (pinfunction "A_2") (pintype "unspecified"))
      (node (ref "SW13") (pin "1") (pinfunction "1_1") (pintype "unspecified"))
    )
    (net (code "32") (name "Net-(D14-A)") (class "Default")
      (node (ref "D14") (pin "2") (pinfunction "A_2") (pintype "unspecified"))
      (node (ref "D4") (pin "1") (pinfunction "K_1") (pintype "unspecified"))
      (node (ref "SW4") (pin "1") (pinfunction "1_1") (pintype "unspecified"))
    )
    (net (code "33") (name "Net-(D14-K)") (class "Default")
      (node (ref "D14") (pin "1") (pinfunction "K_1") (pintype "unspecified"))
      (node (ref "D24") (pin "2") (pinfunction "A_2") (pintype "unspecified"))
      (node (ref "SW14") (pin "1") (pinfunction "1_1") (pintype "unspecified"))
    )
    (net (code "34") (name "Net-(D15-A)") (class "Default")
      (node (ref "D15") (pin "2") (pinfunction "A_2") (pintype "unspecified"))
      (node (ref "D5") (pin "1") (pinfunction "K_1") (pintype "unspecified"))
      (node (ref "SW5") (pin "1") (pinfunction "1_1") (pintype "unspecified"))
    )
    (net (code "35") (name "Net-(D15-K)") (class "Default")
      (node (ref "D15") (pin "1") (pinfunction "K_1") (pintype "unspecified"))
      (node (ref "D25") (pin "2") (pinfunction "A_2") (pintype "unspecified"))
      (node (ref "SW15") (pin "1") (pinfunction "1_1") (pintype "unspecified"))
    )
    (net (code "36") (name "Net-(D16-K)") (class "Default")
      (node (ref "D16") (pin "1") (pinfunction "K_1") (pintype "unspecified"))
      (node (ref "D26") (pin "2") (pinfunction "A_2") (pintype "unspecified"))
      (node (ref "SW16") (pin "1") (pinfunction "1_1") (pintype "unspecified"))
    )
    (net (code "37") (name "Net-(D21-K)") (class "Default")
      (node (ref "D21") (pin "1") (pinfunction "K_1") (pintype "unspecified"))
      (node (ref "D31") (pin "2") (pinfunction "A_2") (pintype "unspecified"))
      (node (ref "SW21") (pin "1") (pinfunction "1_1") (pintype "unspecified"))
    )
    (net (code "38") (name "Net-(D22-K)") (class "Default")
      (node (ref "D22") (pin "1") (pinfunction "K_1") (pintype "unspecified"))
      (node (ref "D32") (pin "2") (pinfunction "A_2") (pintype "unspecified"))
      (node (ref "SW22") (pin "1") (pinfunction "1_1") (pintype "unspecified"))
    )
    (net (code "39") (name "Net-(D23-K)") (class "Default")
      (node (ref "D23") (pin "1") (pinfunction "K_1") (pintype "unspecified"))
      (node (ref "D33") (pin "2") (pinfunction "A_2") (pintype "unspecified"))
      (node (ref "SW23") (pin "1") (pinfunction "1_1") (pintype "unspecified"))
    )
    (net (code "40") (name "Net-(D24-K)") (class "Default")
      (node (ref "D24") (pin "1") (pinfunction "K_1") (pintype "unspecified"))
      (node (ref "D34") (pin "2") (pinfunction "A_2") (pintype "unspecified"))
      (node (ref "SW24") (pin "1") (pinfunction "1_1") (pintype "unspecified"))
    )
    (net (code "41") (name "Net-(D25-K)") (class "Default")
      (node (ref "D25") (pin "1") (pinfunction "K_1") (pintype "unspecified"))
      (node (ref "D35") (pin "2") (pinfunction "A_2") (pintype "unspecified"))
      (node (ref "SW25") (pin "1") (pinfunction "1_1") (pintype "unspecified"))
    )
    (net (code "42") (name "Net-(D26-K)") (class "Default")
      (node (ref "D26") (pin "1") (pinfunction "K_1") (pintype "unspecified"))
      (node (ref "D36") (pin "2") (pinfunction "A_2") (pintype "unspecified"))
      (node (ref "SW26") (pin "1") (pinfunction "1_1") (pintype "unspecified"))
    )
    (net (code "43") (name "Net-(D31-K)") (class "Default")
      (node (ref "D31") (pin "1") (pinfunction "K_1") (pintype "unspecified"))
      (node (ref "D41") (pin "2") (pinfunction "A_2") (pintype "unspecified"))
      (node (ref "SW31") (pin "1") (pinfunction "1_1") (pintype "unspecified"))
    )
    (net (code "44") (name "Net-(D32-K)") (class "Default")
      (node (ref "D32") (pin "1") (pinfunction "K_1") (pintype "unspecified"))
      (node (ref "D42") (pin "2") (pinfunction "A_2") (pintype "unspecified"))
      (node (ref "SW32") (pin "1") (pinfunction "1_1") (pintype "unspecified"))
    )
    (net (code "45") (name "Net-(D33-K)") (class "Default")
      (node (ref "D33") (pin "1") (pinfunction "K_1") (pintype "unspecified"))
      (node (ref "D43") (pin "2") (pinfunction "A_2") (pintype "unspecified"))
      (node (ref "SW33") (pin "1") (pinfunction "1_1") (pintype "unspecified"))
    )
    (net (code "46") (name "Net-(D34-K)") (class "Default")
      (node (ref "D34") (pin "1") (pinfunction "K_1") (pintype "unspecified"))
      (node (ref "D44") (pin "2") (pinfunction "A_2") (pintype "unspecified"))
      (node (ref "SW34") (pin "1") (pinfunction "1_1") (pintype "unspecified"))
    )
    (net (code "47") (name "Net-(D35-K)") (class "Default")
      (node (ref "D35") (pin "1") (pinfunction "K_1") (pintype "unspecified"))
      (node (ref "D45") (pin "2") (pinfunction "A_2") (pintype "unspecified"))
      (node (ref "SW35") (pin "1") (pinfunction "1_1") (pintype "unspecified"))
    )
    (net (code "48") (name "Net-(D36-K)") (class "Default")
      (node (ref "D36") (pin "1") (pinfunction "K_1") (pintype "unspecified"))
      (node (ref "D46") (pin "2") (pinfunction "A_2") (pintype "unspecified"))
      (node (ref "SW36") (pin "1") (pinfunction "1_1") (pintype "unspecified"))
    )
    (net (code "49") (name "Net-(D41-K)") (class "Default")
      (node (ref "D41") (pin "1") (pinfunction "K_1") (pintype "unspecified"))
      (node (ref "D51") (pin "2") (pinfunction "A_2") (pintype "unspecified"))
      (node (ref "SW41") (pin "1") (pinfunction "1_1") (pintype "unspecified"))
    )
    (net (code "50") (name "Net-(D42-K)") (class "Default")
      (node (ref "D42") (pin "1") (pinfunction "K_1") (pintype "unspecified"))
      (node (ref "D52") (pin "2") (pinfunction "A_2") (pintype "unspecified"))
      (node (ref "SW42") (pin "1") (pinfunction "1_1") (pintype "unspecified"))
    )
    (net (code "51") (name "Net-(D43-K)") (class "Default")
      (node (ref "D43") (pin "1") (pinfunction "K_1") (pintype "unspecified"))
      (node (ref "D53") (pin "2") (pinfunction "A_2") (pintype "unspecified"))
      (node (ref "SW43") (pin "1") (pinfunction "1_1") (pintype "unspecified"))
    )
    (net (code "52") (name "Net-(D44-K)") (class "Default")
      (node (ref "D44") (pin "1") (pinfunction "K_1") (pintype "unspecified"))
      (node (ref "D54") (pin "2") (pinfunction "A_2") (pintype "unspecified"))
      (node (ref "SW44") (pin "1") (pinfunction "1_1") (pintype "unspecified"))
    )
    (net (code "53") (name "Net-(D45-K)") (class "Default")
      (node (ref "D45") (pin "1") (pinfunction "K_1") (pintype "unspecified"))
      (node (ref "D55") (pin "2") (pinfunction "A_2") (pintype "unspecified"))
      (node (ref "SW45") (pin "1") (pinfunction "1_1") (pintype "unspecified"))
    )
    (net (code "54") (name "Net-(D46-K)") (class "Default")
      (node (ref "D46") (pin "1") (pinfunction "K_1") (pintype "unspecified"))
      (node (ref "D56") (pin "2") (pinfunction "A_2") (pintype "unspecified"))
      (node (ref "SW46") (pin "1") (pinfunction "1_1") (pintype "unspecified"))
    )
    (net (code "55") (name "Net-(D47-K)") (class "Default")
      (node (ref "D47") (pin "1") (pinfunction "K_1") (pintype "unspecified"))
      (node (ref "D57") (pin "2") (pinfunction "A_2") (pintype "unspecified"))
      (node (ref "SW47") (pin "1") (pinfunction "1_1") (pintype "unspecified"))
    )
    (net (code "56") (name "Net-(D48-K)") (class "Default")
      (node (ref "D48") (pin "1") (pinfunction "K_1") (pintype "unspecified"))
      (node (ref "D58") (pin "2") (pinfunction "A_2") (pintype "unspecified"))
      (node (ref "SW48") (pin "1") (pinfunction "1_1") (pintype "unspecified"))
    )
    (net (code "57") (name "Net-(D51-K)") (class "Default")
      (node (ref "D51") (pin "1") (pinfunction "K_1") (pintype "unspecified"))
      (node (ref "D61") (pin "2") (pinfunction "A_2") (pintype "unspecified"))
      (node (ref "SW51") (pin "1") (pinfunction "1_1") (pintype "unspecified"))
    )
    (net (code "58") (name "Net-(D52-K)") (class "Default")
      (node (ref "D52") (pin "1") (pinfunction "K_1") (pintype "unspecified"))
      (node (ref "D62") (pin "2") (pinfunction "A_2") (pintype "unspecified"))
      (node (ref "SW52") (pin "1") (pinfunction "1_1") (pintype "unspecified"))
    )
    (net (code "59") (name "Net-(D53-K)") (class "Default")
      (node (ref "D53") (pin "1") (pinfunction "K_1") (pintype "unspecified"))
      (node (ref "D63") (pin "2") (pinfunction "A_2") (pintype "unspecified"))
      (node (ref "SW53") (pin "1") (pinfunction "1_1") (pintype "unspecified"))
    )
    (net (code "60") (name "Net-(D54-K)") (class "Default")
      (node (ref "D54") (pin "1") (pinfunction "K_1") (pintype "unspecified"))
      (node (ref "D64") (pin "2") (pinfunction "A_2") (pintype "unspecified"))
      (node (ref "SW54") (pin "1") (pinfunction "1_1") (pintype "unspecified"))
    )
    (net (code "61") (name "Net-(D55-K)") (class "Default")
      (node (ref "D55") (pin "1") (pinfunction "K_1") (pintype "unspecified"))
      (node (ref "D65") (pin "2") (pinfunction "A_2") (pintype "unspecified"))
      (node (ref "SW55") (pin "1") (pinfunction "1_1") (pintype "unspecified"))
    )
    (net (code "62") (name "Net-(D56-K)") (class "Default")
      (node (ref "D56") (pin "1") (pinfunction "K_1") (pintype "unspecified"))
      (node (ref "D66") (pin "2") (pinfunction "A_2") (pintype "unspecified"))
      (node (ref "SW56") (pin "1") (pinfunction "1_1") (pintype "unspecified"))
    )
    (net (code "63") (name "Net-(D57-K)") (class "Default")
      (node (ref "D57") (pin "1") (pinfunction "K_1") (pintype "unspecified"))
      (node (ref "D67") (pin "2") (pinfunction "A_2") (pintype "unspecified"))
      (node (ref "SW57") (pin "1") (pinfunction "1_1") (pintype "unspecified"))
    )
    (net (code "64") (name "Net-(D58-K)") (class "Default")
      (node (ref "D58") (pin "1") (pinfunction "K_1") (pintype "unspecified"))
      (node (ref "D68") (pin "2") (pinfunction "A_2") (pintype "unspecified"))
      (node (ref "SW58") (pin "1") (pinfunction "1_1") (pintype "unspecified"))
    )
    (net (code "65") (name "Net-(D61-K)") (class "Default")
      (node (ref "D61") (pin "1") (pinfunction "K_1") (pintype "unspecified"))
      (node (ref "D71") (pin "2") (pinfunction "A_2") (pintype "unspecified"))
      (node (ref "SW61") (pin "1") (pinfunction "1_1") (pintype "unspecified"))
    )
    (net (code "66") (name "Net-(D62-K)") (class "Default")
      (node (ref "D62") (pin "1") (pinfunction "K_1") (pintype "unspecified"))
      (node (ref "D72") (pin "2") (pinfunction "A_2") (pintype "unspecified"))
      (node (ref "SW62") (pin "1") (pinfunction "1_1") (pintype "unspecified"))
    )
    (net (code "67") (name "Net-(D63-K)") (class "Default")
      (node (ref "D63") (pin "1") (pinfunction "K_1") (pintype "unspecified"))
      (node (ref "D73") (pin "2") (pinfunction "A_2") (pintype "unspecified"))
      (node (ref "SW63") (pin "1") (pinfunction "1_1") (pintype "unspecified"))
    )
    (net (code "68") (name "Net-(D64-K)") (class "Default")
      (node (ref "D64") (pin "1") (pinfunction "K_1") (pintype "unspecified"))
      (node (ref "D74") (pin "2") (pinfunction "A_2") (pintype "unspecified"))
      (node (ref "SW64") (pin "1") (pinfunction "1_1") (pintype "unspecified"))
    )
    (net (code "69") (name "Net-(D65-K)") (class "Default")
      (node (ref "D65") (pin "1") (pinfunction "K_1") (pintype "unspecified"))
      (node (ref "D75") (pin "2") (pinfunction "A_2") (pintype "unspecified"))
      (node (ref "SW65") (pin "1") (pinfunction "1_1") (pintype "unspecified"))
    )
    (net (code "70") (name "Net-(D66-K)") (class "Default")
      (node (ref "D66") (pin "1") (pinfunction "K_1") (pintype "unspecified"))
      (node (ref "D76") (pin "2") (pinfunction "A_2") (pintype "unspecified"))
      (node (ref "SW66") (pin "1") (pinfunction "1_1") (pintype "unspecified"))
    )
    (net (code "71") (name "Net-(D67-K)") (class "Default")
      (node (ref "D67") (pin "1") (pinfunction "K_1") (pintype "unspecified"))
      (node (ref "D77") (pin "2") (pinfunction "A_2") (pintype "unspecified"))
      (node (ref "SW67") (pin "1") (pinfunction "1_1") (pintype "unspecified"))
    )
    (net (code "72") (name "Net-(D68-K)") (class "Default")
      (node (ref "D68") (pin "1") (pinfunction "K_1") (pintype "unspecified"))
      (node (ref "D78") (pin "2") (pinfunction "A_2") (pintype "unspecified"))
      (node (ref "SW68") (pin "1") (pinfunction "1_1") (pintype "unspecified"))
    )
    (net (code "73") (name "Net-(D71-K)") (class "Default")
      (node (ref "D71") (pin "1") (pinfunction "K_1") (pintype "unspecified"))
      (node (ref "SW71") (pin "1") (pinfunction "1_1") (pintype "unspecified"))
    )
    (net (code "74") (name "Net-(D72-K)") (class "Default")
      (node (ref "D72") (pin "1") (pinfunction "K_1") (pintype "unspecified"))
      (node (ref "SW72") (pin "1") (pinfunction "1_1") (pintype "unspecified"))
    )
    (net (code "75") (name "Net-(D73-K)") (class "Default")
      (node (ref "D73") (pin "1") (pinfunction "K_1") (pintype "unspecified"))
      (node (ref "SW73") (pin "1") (pinfunction "1_1") (pintype "unspecified"))
    )
    (net (code "76") (name "Net-(D74-K)") (class "Default")
      (node (ref "D74") (pin "1") (pinfunction "K_1") (pintype "unspecified"))
      (node (ref "SW74") (pin "1") (pinfunction "1_1") (pintype "unspecified"))
    )
    (net (code "77") (name "Net-(D75-K)") (class "Default")
      (node (ref "D75") (pin "1") (pinfunction "K_1") (pintype "unspecified"))
      (node (ref "SW75") (pin "1") (pinfunction "1_1") (pintype "unspecified"))
    )
    (net (code "78") (name "Net-(D76-K)") (class "Default")
      (node (ref "D76") (pin "1") (pinfunction "K_1") (pintype "unspecified"))
      (node (ref "SW76") (pin "1") (pinfunction "1_1") (pintype "unspecified"))
    )
    (net (code "79") (name "Net-(D77-K)") (class "Default")
      (node (ref "D77") (pin "1") (pinfunction "K_1") (pintype "unspecified"))
      (node (ref "SW77") (pin "1") (pinfunction "1_1") (pintype "unspecified"))
    )
    (net (code "80") (name "Net-(D78-K)") (class "Default")
      (node (ref "D78") (pin "1") (pinfunction "K_1") (pintype "unspecified"))
      (node (ref "SW78") (pin "1") (pinfunction "1_1") (pintype "unspecified"))
    )
    (net (code "81") (name "Net-(LED1-C)") (class "Default")
      (node (ref "LED1") (pin "2") (pinfunction "C_2") (pintype "input"))
      (node (ref "R1") (pin "1") (pinfunction "1_1") (pintype "unspecified"))
    )
    (net (code "82") (name "Net-(LED2-C)") (class "Default")
      (node (ref "LED2") (pin "2") (pinfunction "C_2") (pintype "input"))
      (node (ref "R2") (pin "1") (pinfunction "1_1") (pintype "unspecified"))
    )
    (net (code "83") (name "Net-(LED3-C)") (class "Default")
      (node (ref "LED3") (pin "2") (pinfunction "C_2") (pintype "input"))
      (node (ref "R3") (pin "1") (pinfunction "1_1") (pintype "unspecified"))
    )
    (net (code "84") (name "Net-(LED4-C)") (class "Default")
      (node (ref "LED4") (pin "2") (pinfunction "C_2") (pintype "input"))
      (node (ref "R4") (pin "1") (pinfunction "1_1") (pintype "unspecified"))
    )
    (net (code "85") (name "Net-(LED5-C)") (class "Default")
      (node (ref "LED5") (pin "2") (pinfunction "C_2") (pintype "input"))
      (node (ref "R5") (pin "1") (pinfunction "1_1") (pintype "unspecified"))
    )
    (net (code "86") (name "Net-(LED6-C)") (class "Default")
      (node (ref "LED6") (pin "2") (pinfunction "C_2") (pintype "input"))
      (node (ref "R6") (pin "1") (pinfunction "1_1") (pintype "unspecified"))
    )
    (net (code "87") (name "Net-(SW1-Pad4)") (class "Default")
      (node (ref "SW1") (pin "4") (pinfunction "4_4") (pintype "unspecified"))
      (node (ref "SW2") (pin "3") (pinfunction "3_3") (pintype "unspecified"))
    )
    (net (code "88") (name "Net-(SW2-Pad4)") (class "Default")
      (node (ref "SW2") (pin "4") (pinfunction "4_4") (pintype "unspecified"))
      (node (ref "SW3") (pin "3") (pinfunction "3_3") (pintype "unspecified"))
    )
    (net (code "89") (name "Net-(SW3-Pad4)") (class "Default")
      (node (ref "SW3") (pin "4") (pinfunction "4_4") (pintype "unspecified"))
      (node (ref "SW4") (pin "3") (pinfunction "3_3") (pintype "unspecified"))
    )
    (net (code "90") (name "Net-(SW4-Pad4)") (class "Default")
      (node (ref "SW4") (pin "4") (pinfunction "4_4") (pintype "unspecified"))
      (node (ref "SW5") (pin "3") (pinfunction "3_3") (pintype "unspecified"))
    )
    (net (code "91") (name "Net-(SW11-Pad4)") (class "Default")
      (node (ref "SW11") (pin "4") (pinfunction "4_4") (pintype "unspecified"))
      (node (ref "SW12") (pin "3") (pinfunction "3_3") (pintype "unspecified"))
    )
    (net (code "92") (name "Net-(SW12-Pad4)") (class "Default")
      (node (ref "SW12") (pin "4") (pinfunction "4_4") (pintype "unspecified"))
      (node (ref "SW13") (pin "3") (pinfunction "3_3") (pintype "unspecified"))
    )
    (net (code "93") (name "Net-(SW13-Pad4)") (class "Default")
      (node (ref "SW13") (pin "4") (pinfunction "4_4") (pintype "unspecified"))
      (node (ref "SW14") (pin "3") (pinfunction "3_3") (pintype "unspecified"))
    )
    (net (code "94") (name "Net-(SW14-Pad4)") (class "Default")
      (node (ref "SW14") (pin "4") (pinfunction "4_4") (pintype "unspecified"))
      (node (ref "SW15") (pin "3") (pinfunction "3_3") (pintype "unspecified"))
    )
    (net (code "95") (name "Net-(SW15-Pad4)") (class "Default")
      (node (ref "SW15") (pin "4") (pinfunction "4_4") (pintype "unspecified"))
      (node (ref "SW16") (pin "3") (pinfunction "3_3") (pintype "unspecified"))
    )
    (net (code "96") (name "Net-(SW21-Pad4)") (class "Default")
      (node (ref "SW21") (pin "4") (pinfunction "4_4") (pintype "unspecified"))
      (node (ref "SW22") (pin "3") (pinfunction "3_3") (pintype "unspecified"))
    )
    (net (code "97") (name "Net-(SW22-Pad4)") (class "Default")
      (node (ref "SW22") (pin "4") (pinfunction "4_4") (pintype "unspecified"))
      (node (ref "SW23") (pin "3") (pinfunction "3_3") (pintype "unspecified"))
    )
    (net (code "98") (name "Net-(SW23-Pad4)") (class "Default")
      (node (ref "SW23") (pin "4") (pinfunction "4_4") (pintype "unspecified"))
      (node (ref "SW24") (pin "3") (pinfunction "3_3") (pintype "unspecified"))
    )
    (net (code "99") (name "Net-(SW24-Pad4)") (class "Default")
      (node (ref "SW24") (pin "4") (pinfunction "4_4") (pintype "unspecified"))
      (node (ref "SW25") (pin "3") (pinfunction "3_3") (pintype "unspecified"))
    )
    (net (code "100") (name "Net-(SW25-Pad4)") (class "Default")
      (node (ref "SW25") (pin "4") (pinfunction "4_4") (pintype "unspecified"))
      (node (ref "SW26") (pin "3") (pinfunction "3_3") (pintype "unspecified"))
    )
    (net (code "101") (name "Net-(SW31-Pad4)") (class "Default")
      (node (ref "SW31") (pin "4") (pinfunction "4_4") (pintype "unspecified"))
      (node (ref "SW32") (pin "3") (pinfunction "3_3") (pintype "unspecified"))
    )
    (net (code "102") (name "Net-(SW32-Pad4)") (class "Default")
      (node (ref "SW32") (pin "4") (pinfunction "4_4") (pintype "unspecified"))
      (node (ref "SW33") (pin "3") (pinfunction "3_3") (pintype "unspecified"))
    )
    (net (code "103") (name "Net-(SW33-Pad4)") (class "Default")
      (node (ref "SW33") (pin "4") (pinfunction "4_4") (pintype "unspecified"))
      (node (ref "SW34") (pin "3") (pinfunction "3_3") (pintype "unspecified"))
    )
    (net (code "104") (name "Net-(SW34-Pad4)") (class "Default")
      (node (ref "SW34") (pin "4") (pinfunction "4_4") (pintype "unspecified"))
      (node (ref "SW35") (pin "3") (pinfunction "3_3") (pintype "unspecified"))
    )
    (net (code "105") (name "Net-(SW35-Pad4)") (class "Default")
      (node (ref "SW35") (pin "4") (pinfunction "4_4") (pintype "unspecified"))
      (node (ref "SW36") (pin "3") (pinfunction "3_3") (pintype "unspecified"))
    )
    (net (code "106") (name "Net-(SW41-Pad4)") (class "Default")
      (node (ref "SW41") (pin "4") (pinfunction "4_4") (pintype "unspecified"))
      (node (ref "SW42") (pin "3") (pinfunction "3_3") (pintype "unspecified"))
    )
    (net (code "107") (name "Net-(SW42-Pad4)") (class "Default")
      (node (ref "SW42") (pin "4") (pinfunction "4_4") (pintype "unspecified"))
      (node (ref "SW43") (pin "3") (pinfunction "3_3") (pintype "unspecified"))
    )
    (net (code "108") (name "Net-(SW43-Pad4)") (class "Default")
      (node (ref "SW43") (pin "4") (pinfunction "4_4") (pintype "unspecified"))
      (node (ref "SW44") (pin "3") (pinfunction "3_3") (pintype "unspecified"))
    )
    (net (code "109") (name "Net-(SW44-Pad4)") (class "Default")
      (node (ref "SW44") (pin "4") (pinfunction "4_4") (pintype "unspecified"))
      (node (ref "SW45") (pin "3") (pinfunction "3_3") (pintype "unspecified"))
    )
    (net (code "110") (name "Net-(SW45-Pad4)") (class "Default")
      (node (ref "SW45") (pin "4") (pinfunction "4_4") (pintype "unspecified"))
      (node (ref "SW46") (pin "3") (pinfunction "3_3") (pintype "unspecified"))
    )
    (net (code "111") (name "Net-(SW46-Pad4)") (class "Default")
      (node (ref "SW46") (pin "4") (pinfunction "4_4") (pintype "unspecified"))
      (node (ref "SW47") (pin "3") (pinfunction "3_3") (pintype "unspecified"))
    )
    (net (code "112") (name "Net-(SW47-Pad4)") (class "Default")
      (node (ref "SW47") (pin "4") (pinfunction "4_4") (pintype "unspecified"))
      (node (ref "SW48") (pin "3") (pinfunction "3_3") (pintype "unspecified"))
    )
    (net (code "113") (name "Net-(SW51-Pad4)") (class "Default")
      (node (ref "SW51") (pin "4") (pinfunction "4_4") (pintype "unspecified"))
      (node (ref "SW52") (pin "3") (pinfunction "3_3") (pintype "unspecified"))
    )
    (net (code "114") (name "Net-(SW52-Pad4)") (class "Default")
      (node (ref "SW52") (pin "4") (pinfunction "4_4") (pintype "unspecified"))
      (node (ref "SW53") (pin "3") (pinfunction "3_3") (pintype "unspecified"))
    )
    (net (code "115") (name "Net-(SW53-Pad4)") (class "Default")
      (node (ref "SW53") (pin "4") (pinfunction "4_4") (pintype "unspecified"))
      (node (ref "SW54") (pin "3") (pinfunction "3_3") (pintype "unspecified"))
    )
    (net (code "116") (name "Net-(SW54-Pad4)") (class "Default")
      (node (ref "SW54") (pin "4") (pinfunction "4_4") (pintype "unspecified"))
      (node (ref "SW55") (pin "3") (pinfunction "3_3") (pintype "unspecified"))
    )
    (net (code "117") (name "Net-(SW55-Pad4)") (class "Default")
      (node (ref "SW55") (pin "4") (pinfunction "4_4") (pintype "unspecified"))
      (node (ref "SW56") (pin "3") (pinfunction "3_3") (pintype "unspecified"))
    )
    (net (code "118") (name "Net-(SW56-Pad4)") (class "Default")
      (node (ref "SW56") (pin "4") (pinfunction "4_4") (pintype "unspecified"))
      (node (ref "SW57") (pin "3") (pinfunction "3_3") (pintype "unspecified"))
    )
    (net (code "119") (name "Net-(SW57-Pad4)") (class "Default")
      (node (ref "SW57") (pin "4") (pinfunction "4_4") (pintype "unspecified"))
      (node (ref "SW58") (pin "3") (pinfunction "3_3") (pintype "unspecified"))
    )
    (net (code "120") (name "Net-(SW61-Pad4)") (class "Default")
      (node (ref "SW61") (pin "4") (pinfunction "4_4") (pintype "unspecified"))
      (node (ref "SW62") (pin "3") (pinfunction "3_3") (pintype "unspecified"))
    )
    (net (code "121") (name "Net-(SW62-Pad4)") (class "Default")
      (node (ref "SW62") (pin "4") (pinfunction "4_4") (pintype "unspecified"))
      (node (ref "SW63") (pin "3") (pinfunction "3_3") (pintype "unspecified"))
    )
    (net (code "122") (name "Net-(SW63-Pad4)") (class "Default")
      (node (ref "SW63") (pin "4") (pinfunction "4_4") (pintype "unspecified"))
      (node (ref "SW64") (pin "3") (pinfunction "3_3") (pintype "unspecified"))
    )
    (net (code "123") (name "Net-(SW64-Pad4)") (class "Default")
      (node (ref "SW64") (pin "4") (pinfunction "4_4") (pintype "unspecified"))
      (node (ref "SW65") (pin "3") (pinfunction "3_3") (pintype "unspecified"))
    )
    (net (code "124") (name "Net-(SW65-Pad4)") (class "Default")
      (node (ref "SW65") (pin "4") (pinfunction "4_4") (pintype "unspecified"))
      (node (ref "SW66") (pin "3") (pinfunction "3_3") (pintype "unspecified"))
    )
    (net (code "125") (name "Net-(SW66-Pad4)") (class "Default")
      (node (ref "SW66") (pin "4") (pinfunction "4_4") (pintype "unspecified"))
      (node (ref "SW67") (pin "3") (pinfunction "3_3") (pintype "unspecified"))
    )
    (net (code "126") (name "Net-(SW67-Pad4)") (class "Default")
      (node (ref "SW67") (pin "4") (pinfunction "4_4") (pintype "unspecified"))
      (node (ref "SW68") (pin "3") (pinfunction "3_3") (pintype "unspecified"))
    )
    (net (code "127") (name "Net-(SW71-Pad4)") (class "Default")
      (node (ref "SW71") (pin "4") (pinfunction "4_4") (pintype "unspecified"))
      (node (ref "SW72") (pin "3") (pinfunction "3_3") (pintype "unspecified"))
    )
    (net (code "128") (name "Net-(SW72-Pad4)") (class "Default")
      (node (ref "SW72") (pin "4") (pinfunction "4_4") (pintype "unspecified"))
      (node (ref "SW73") (pin "3") (pinfunction "3_3") (pintype "unspecified"))
    )
    (net (code "129") (name "Net-(SW73-Pad4)") (class "Default")
      (node (ref "SW73") (pin "4") (pinfunction "4_4") (pintype "unspecified"))
      (node (ref "SW74") (pin "3") (pinfunction "3_3") (pintype "unspecified"))
    )
    (net (code "130") (name "Net-(SW74-Pad4)") (class "Default")
      (node (ref "SW74") (pin "4") (pinfunction "4_4") (pintype "unspecified"))
      (node (ref "SW75") (pin "3") (pinfunction "3_3") (pintype "unspecified"))
    )
    (net (code "131") (name "Net-(SW75-Pad4)") (class "Default")
      (node (ref "SW75") (pin "4") (pinfunction "4_4") (pintype "unspecified"))
      (node (ref "SW76") (pin "3") (pinfunction "3_3") (pintype "unspecified"))
    )
    (net (code "132") (name "Net-(SW76-Pad4)") (class "Default")
      (node (ref "SW76") (pin "4") (pinfunction "4_4") (pintype "unspecified"))
      (node (ref "SW77") (pin "3") (pinfunction "3_3") (pintype "unspecified"))
    )
    (net (code "133") (name "Net-(SW77-Pad4)") (class "Default")
      (node (ref "SW77") (pin "4") (pinfunction "4_4") (pintype "unspecified"))
      (node (ref "SW78") (pin "3") (pinfunction "3_3") (pintype "unspecified"))
    )
    (net (code "134") (name "Net-(U1-S)") (class "Default")
      (node (ref "R1") (pin "2") (pinfunction "2_2") (pintype "unspecified"))
      (node (ref "U1") (pin "2") (pinfunction "S_2") (pintype "unspecified"))
    )
    (net (code "135") (name "Net-(U2-S)") (class "Default")
      (node (ref "R2") (pin "2") (pinfunction "2_2") (pintype "unspecified"))
      (node (ref "U2") (pin "2") (pinfunction "S_2") (pintype "unspecified"))
    )
    (net (code "136") (name "Net-(U3-S)") (class "Default")
      (node (ref "R3") (pin "2") (pinfunction "2_2") (pintype "unspecified"))
      (node (ref "U3") (pin "2") (pinfunction "S_2") (pintype "unspecified"))
    )
    (net (code "137") (name "Net-(U4-S)") (class "Default")
      (node (ref "R4") (pin "2") (pinfunction "2_2") (pintype "unspecified"))
      (node (ref "U4") (pin "2") (pinfunction "S_2") (pintype "unspecified"))
    )
    (net (code "138") (name "Net-(U5-S)") (class "Default")
      (node (ref "R5") (pin "2") (pinfunction "2_2") (pintype "unspecified"))
      (node (ref "U5") (pin "2") (pinfunction "S_2") (pintype "unspecified"))
    )
    (net (code "139") (name "Net-(U6-S)") (class "Default")
      (node (ref "R6") (pin "2") (pinfunction "2_2") (pintype "unspecified"))
      (node (ref "U6") (pin "2") (pinfunction "S_2") (pintype "unspecified"))
    )
    (net (code "140") (name "VCC") (class "Default")
      (node (ref "CN1") (pin "25") (pinfunction "25_25") (pintype "unspecified"))
      (node (ref "LED1") (pin "1") (pinfunction "A_1") (pintype "input"))
      (node (ref "LED2") (pin "1") (pinfunction "A_1") (pintype "input"))
      (node (ref "LED3") (pin "1") (pinfunction "A_1") (pintype "input"))
      (node (ref "LED4") (pin "1") (pinfunction "A_1") (pintype "input"))
      (node (ref "LED5") (pin "1") (pinfunction "A_1") (pintype "input"))
      (node (ref "LED6") (pin "1") (pinfunction "A_1") (pintype "input"))
      (node (ref "U7") (pin "1") (pinfunction "1_1") (pintype "input"))
    )
    (net (code "141") (name "unconnected-(CN1-Pad24)") (class "Default")
      (node (ref "CN1") (pin "24") (pinfunction "24_24") (pintype "unspecified+no_connect"))
    )
    (net (code "142") (name "unconnected-(SW1-Pad2)") (class "Default")
      (node (ref "SW1") (pin "2") (pinfunction "2_2") (pintype "unspecified"))
    )
    (net (code "143") (name "unconnected-(SW2-Pad2)") (class "Default")
      (node (ref "SW2") (pin "2") (pinfunction "2_2") (pintype "unspecified"))
    )
    (net (code "144") (name "unconnected-(SW3-Pad2)") (class "Default")
      (node (ref "SW3") (pin "2") (pinfunction "2_2") (pintype "unspecified"))
    )
    (net (code "145") (name "unconnected-(SW4-Pad2)") (class "Default")
      (node (ref "SW4") (pin "2") (pinfunction "2_2") (pintype "unspecified"))
    )
    (net (code "146") (name "unconnected-(SW5-Pad2)") (class "Default")
      (node (ref "SW5") (pin "2") (pinfunction "2_2") (pintype "unspecified"))
    )
    (net (code "147") (name "unconnected-(SW5-Pad4)") (class "Default")
      (node (ref "SW5") (pin "4") (pinfunction "4_4") (pintype "unspecified"))
    )
    (net (code "148") (name "unconnected-(SW11-Pad2)") (class "Default")
      (node (ref "SW11") (pin "2") (pinfunction "2_2") (pintype "unspecified"))
    )
    (net (code "149") (name "unconnected-(SW12-Pad2)") (class "Default")
      (node (ref "SW12") (pin "2") (pinfunction "2_2") (pintype "unspecified"))
    )
    (net (code "150") (name "unconnected-(SW13-Pad2)") (class "Default")
      (node (ref "SW13") (pin "2") (pinfunction "2_2") (pintype "unspecified"))
    )
    (net (code "151") (name "unconnected-(SW14-Pad2)") (class "Default")
      (node (ref "SW14") (pin "2") (pinfunction "2_2") (pintype "unspecified"))
    )
    (net (code "152") (name "unconnected-(SW15-Pad2)") (class "Default")
      (node (ref "SW15") (pin "2") (pinfunction "2_2") (pintype "unspecified"))
    )
    (net (code "153") (name "unconnected-(SW16-Pad2)") (class "Default")
      (node (ref "SW16") (pin "2") (pinfunction "2_2") (pintype "unspecified"))
    )
    (net (code "154") (name "unconnected-(SW16-Pad4)") (class "Default")
      (node (ref "SW16") (pin "4") (pinfunction "4_4") (pintype "unspecified"))
    )
    (net (code "155") (name "unconnected-(SW21-Pad2)") (class "Default")
      (node (ref "SW21") (pin "2") (pinfunction "2_2") (pintype "unspecified"))
    )
    (net (code "156") (name "unconnected-(SW22-Pad2)") (class "Default")
      (node (ref "SW22") (pin "2") (pinfunction "2_2") (pintype "unspecified"))
    )
    (net (code "157") (name "unconnected-(SW23-Pad2)") (class "Default")
      (node (ref "SW23") (pin "2") (pinfunction "2_2") (pintype "unspecified"))
    )
    (net (code "158") (name "unconnected-(SW24-Pad2)") (class "Default")
      (node (ref "SW24") (pin "2") (pinfunction "2_2") (pintype "unspecified"))
    )
    (net (code "159") (name "unconnected-(SW25-Pad2)") (class "Default")
      (node (ref "SW25") (pin "2") (pinfunction "2_2") (pintype "unspecified"))
    )
    (net (code "160") (name "unconnected-(SW26-Pad2)") (class "Default")
      (node (ref "SW26") (pin "2") (pinfunction "2_2") (pintype "unspecified"))
    )
    (net (code "161") (name "unconnected-(SW26-Pad4)") (class "Default")
      (node (ref "SW26") (pin "4") (pinfunction "4_4") (pintype "unspecified"))
    )
    (net (code "162") (name "unconnected-(SW31-Pad2)") (class "Default")
      (node (ref "SW31") (pin "2") (pinfunction "2_2") (pintype "unspecified"))
    )
    (net (code "163") (name "unconnected-(SW32-Pad2)") (class "Default")
      (node (ref "SW32") (pin "2") (pinfunction "2_2") (pintype "unspecified"))
    )
    (net (code "164") (name "unconnected-(SW33-Pad2)") (class "Default")
      (node (ref "SW33") (pin "2") (pinfunction "2_2") (pintype "unspecified"))
    )
    (net (code "165") (name "unconnected-(SW34-Pad2)") (class "Default")
      (node (ref "SW34") (pin "2") (pinfunction "2_2") (pintype "unspecified"))
    )
    (net (code "166") (name "unconnected-(SW35-Pad2)") (class "Default")
      (node (ref "SW35") (pin "2") (pinfunction "2_2") (pintype "unspecified"))
    )
    (net (code "167") (name "unconnected-(SW36-Pad2)") (class "Default")
      (node (ref "SW36") (pin "2") (pinfunction "2_2") (pintype "unspecified"))
    )
    (net (code "168") (name "unconnected-(SW36-Pad4)") (class "Default")
      (node (ref "SW36") (pin "4") (pinfunction "4_4") (pintype "unspecified"))
    )
    (net (code "169") (name "unconnected-(SW41-Pad2)") (class "Default")
      (node (ref "SW41") (pin "2") (pinfunction "2_2") (pintype "unspecified"))
    )
    (net (code "170") (name "unconnected-(SW42-Pad2)") (class "Default")
      (node (ref "SW42") (pin "2") (pinfunction "2_2") (pintype "unspecified"))
    )
    (net (code "171") (name "unconnected-(SW43-Pad2)") (class "Default")
      (node (ref "SW43") (pin "2") (pinfunction "2_2") (pintype "unspecified"))
    )
    (net (code "172") (name "unconnected-(SW44-Pad2)") (class "Default")
      (node (ref "SW44") (pin "2") (pinfunction "2_2") (pintype "unspecified"))
    )
    (net (code "173") (name "unconnected-(SW45-Pad2)") (class "Default")
      (node (ref "SW45") (pin "2") (pinfunction "2_2") (pintype "unspecified"))
    )
    (net (code "174") (name "unconnected-(SW46-Pad2)") (class "Default")
      (node (ref "SW46") (pin "2") (pinfunction "2_2") (pintype "unspecified"))
    )
    (net (code "175") (name "unconnected-(SW47-Pad2)") (class "Default")
      (node (ref "SW47") (pin "2") (pinfunction "2_2") (pintype "unspecified"))
    )
    (net (code "176") (name "unconnected-(SW48-Pad2)") (class "Default")
      (node (ref "SW48") (pin "2") (pinfunction "2_2") (pintype "unspecified"))
    )
    (net (code "177") (name "unconnected-(SW48-Pad4)") (class "Default")
      (node (ref "SW48") (pin "4") (pinfunction "4_4") (pintype "unspecified"))
    )
    (net (code "178") (name "unconnected-(SW51-Pad2)") (class "Default")
      (node (ref "SW51") (pin "2") (pinfunction "2_2") (pintype "unspecified"))
    )
    (net (code "179") (name "unconnected-(SW52-Pad2)") (class "Default")
      (node (ref "SW52") (pin "2") (pinfunction "2_2") (pintype "unspecified"))
    )
    (net (code "180") (name "unconnected-(SW53-Pad2)") (class "Default")
      (node (ref "SW53") (pin "2") (pinfunction "2_2") (pintype "unspecified"))
    )
    (net (code "181") (name "unconnected-(SW54-Pad2)") (class "Default")
      (node (ref "SW54") (pin "2") (pinfunction "2_2") (pintype "unspecified"))
    )
    (net (code "182") (name "unconnected-(SW55-Pad2)") (class "Default")
      (node (ref "SW55") (pin "2") (pinfunction "2_2") (pintype "unspecified"))
    )
    (net (code "183") (name "unconnected-(SW56-Pad2)") (class "Default")
      (node (ref "SW56") (pin "2") (pinfunction "2_2") (pintype "unspecified"))
    )
    (net (code "184") (name "unconnected-(SW57-Pad2)") (class "Default")
      (node (ref "SW57") (pin "2") (pinfunction "2_2") (pintype "unspecified"))
    )
    (net (code "185") (name "unconnected-(SW58-Pad2)") (class "Default")
      (node (ref "SW58") (pin "2") (pinfunction "2_2") (pintype "unspecified"))
    )
    (net (code "186") (name "unconnected-(SW58-Pad4)") (class "Default")
      (node (ref "SW58") (pin "4") (pinfunction "4_4") (pintype "unspecified"))
    )
    (net (code "187") (name "unconnected-(SW61-Pad2)") (class "Default")
      (node (ref "SW61") (pin "2") (pinfunction "2_2") (pintype "unspecified"))
    )
    (net (code "188") (name "unconnected-(SW62-Pad2)") (class "Default")
      (node (ref "SW62") (pin "2") (pinfunction "2_2") (pintype "unspecified"))
    )
    (net (code "189") (name "unconnected-(SW63-Pad2)") (class "Default")
      (node (ref "SW63") (pin "2") (pinfunction "2_2") (pintype "unspecified"))
    )
    (net (code "190") (name "unconnected-(SW64-Pad2)") (class "Default")
      (node (ref "SW64") (pin "2") (pinfunction "2_2") (pintype "unspecified"))
    )
    (net (code "191") (name "unconnected-(SW65-Pad2)") (class "Default")
      (node (ref "SW65") (pin "2") (pinfunction "2_2") (pintype "unspecified"))
    )
    (net (code "192") (name "unconnected-(SW66-Pad2)") (class "Default")
      (node (ref "SW66") (pin "2") (pinfunction "2_2") (pintype "unspecified"))
    )
    (net (code "193") (name "unconnected-(SW67-Pad2)") (class "Default")
      (node (ref "SW67") (pin "2") (pinfunction "2_2") (pintype "unspecified"))
    )
    (net (code "194") (name "unconnected-(SW68-Pad2)") (class "Default")
      (node (ref "SW68") (pin "2") (pinfunction "2_2") (pintype "unspecified"))
    )
    (net (code "195") (name "unconnected-(SW68-Pad4)") (class "Default")
      (node (ref "SW68") (pin "4") (pinfunction "4_4") (pintype "unspecified"))
    )
    (net (code "196") (name "unconnected-(SW71-Pad2)") (class "Default")
      (node (ref "SW71") (pin "2") (pinfunction "2_2") (pintype "unspecified"))
    )
    (net (code "197") (name "unconnected-(SW72-Pad2)") (class "Default")
      (node (ref "SW72") (pin "2") (pinfunction "2_2") (pintype "unspecified"))
    )
    (net (code "198") (name "unconnected-(SW73-Pad2)") (class "Default")
      (node (ref "SW73") (pin "2") (pinfunction "2_2") (pintype "unspecified"))
    )
    (net (code "199") (name "unconnected-(SW74-Pad2)") (class "Default")
      (node (ref "SW74") (pin "2") (pinfunction "2_2") (pintype "unspecified"))
    )
    (net (code "200") (name "unconnected-(SW75-Pad2)") (class "Default")
      (node (ref "SW75") (pin "2") (pinfunction "2_2") (pintype "unspecified"))
    )
    (net (code "201") (name "unconnected-(SW76-Pad2)") (class "Default")
      (node (ref "SW76") (pin "2") (pinfunction "2_2") (pintype "unspecified"))
    )
    (net (code "202") (name "unconnected-(SW77-Pad2)") (class "Default")
      (node (ref "SW77") (pin "2") (pinfunction "2_2") (pintype "unspecified"))
    )
    (net (code "203") (name "unconnected-(SW78-Pad2)") (class "Default")
      (node (ref "SW78") (pin "2") (pinfunction "2_2") (pintype "unspecified"))
    )
    (net (code "204") (name "unconnected-(SW78-Pad4)") (class "Default")
      (node (ref "SW78") (pin "4") (pinfunction "4_4") (pintype "unspecified"))
    )
  )
)
